# MOM_teensy-breakout_v04.net
KiCad netlist of a schematic drawn in EAGLE
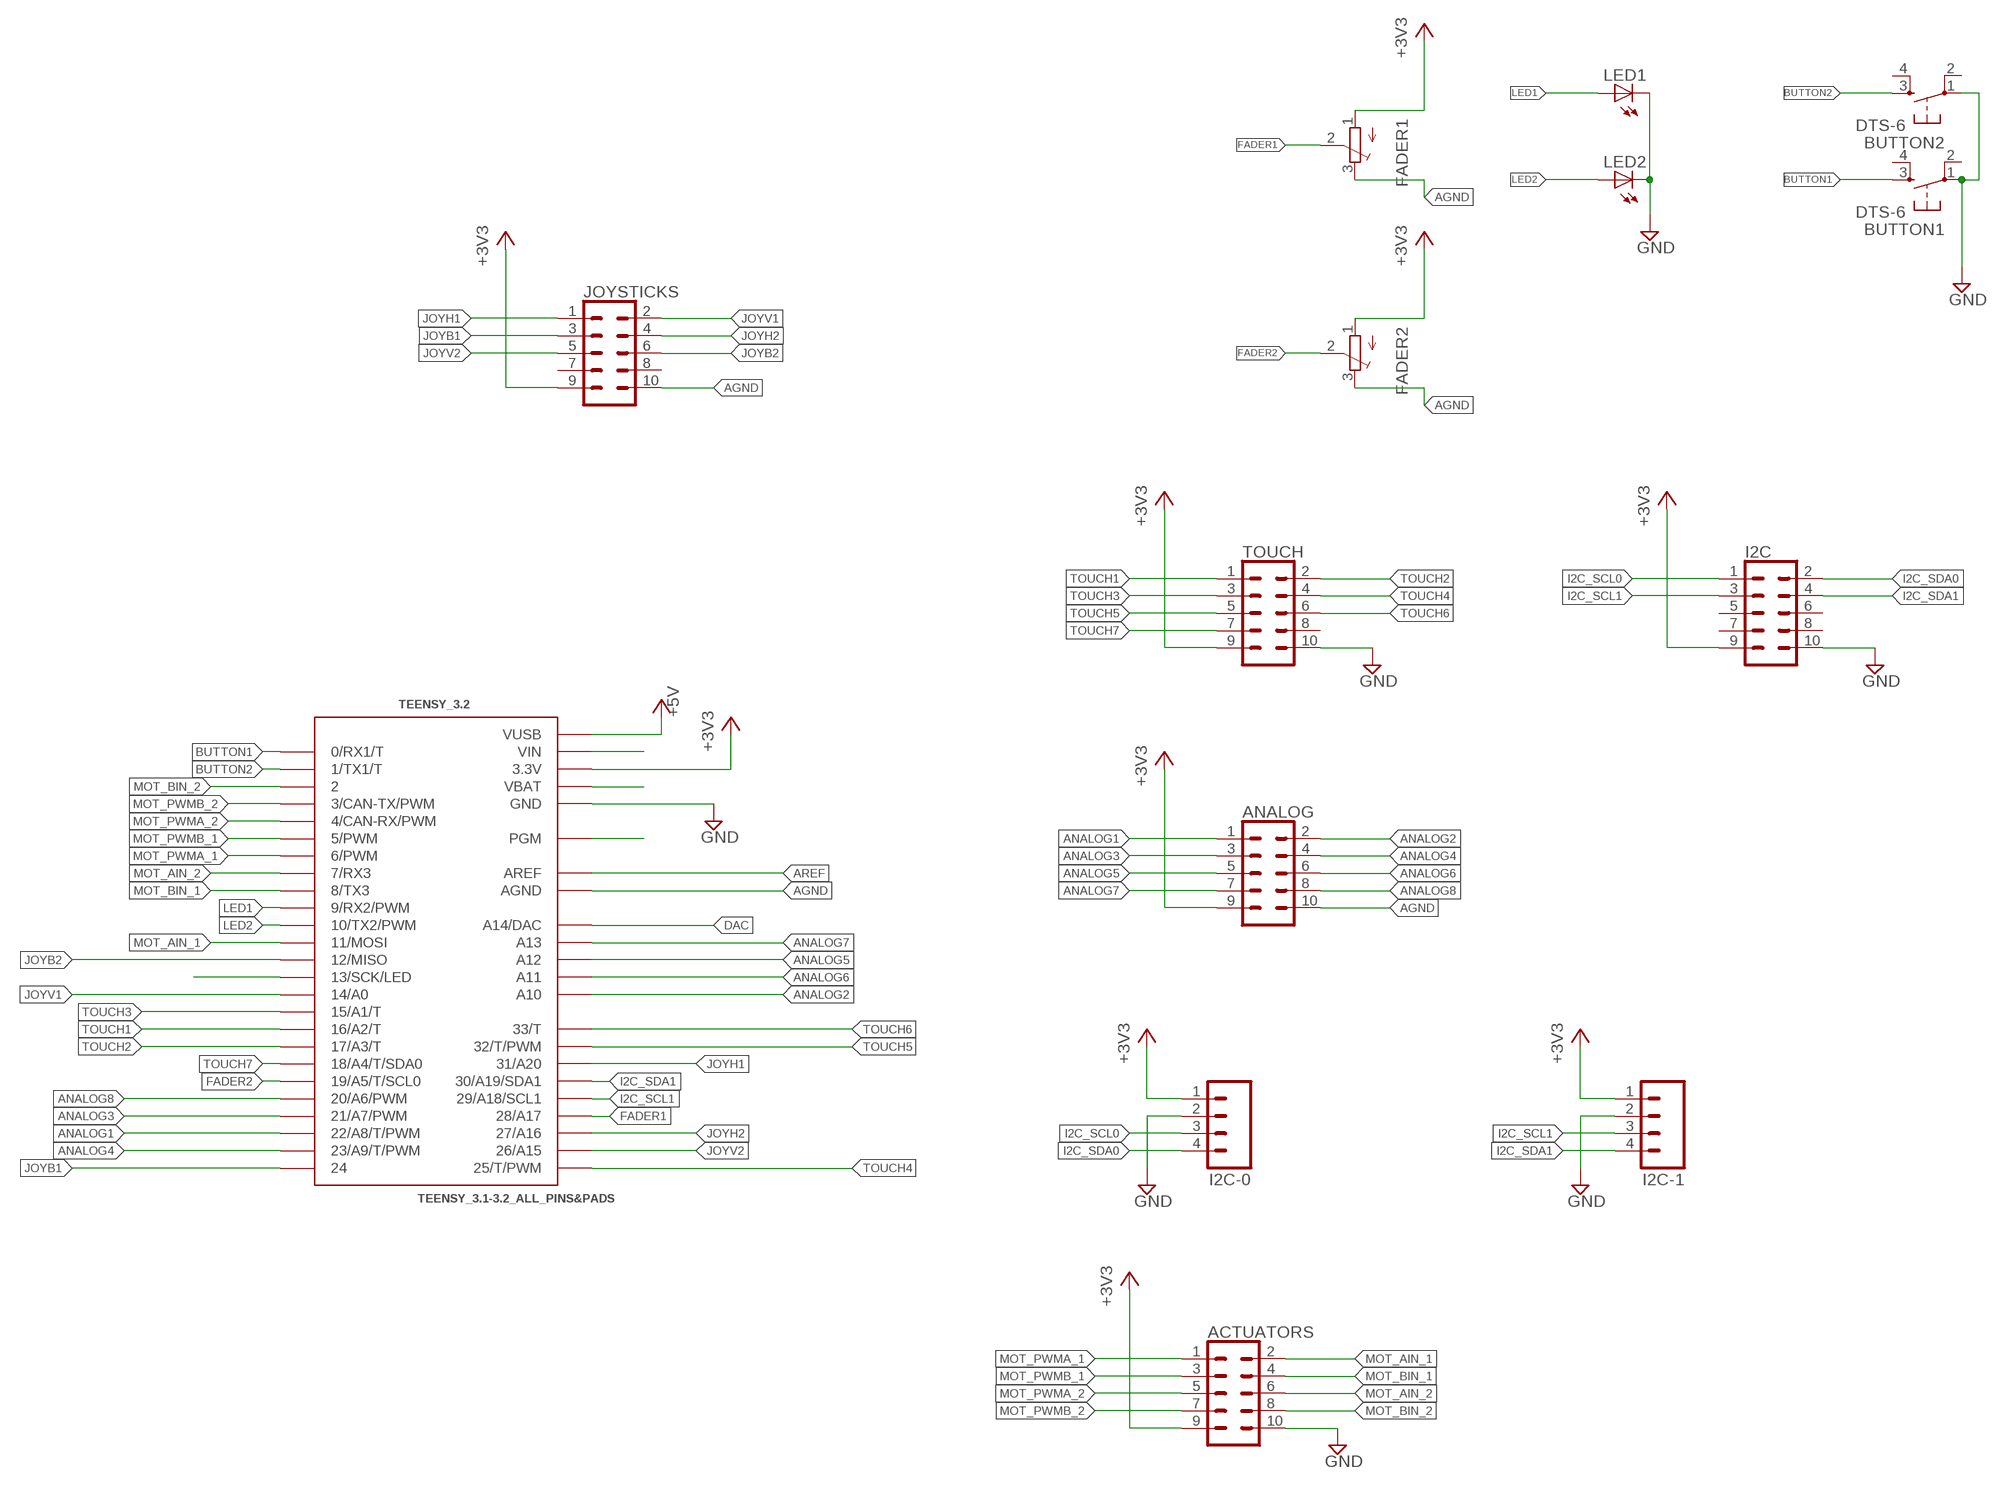
[diagram p0: schematic, sheet 1]

(export (version "E")
  (design (tool "Eeschema 10.0.6"))
  (components
    (comp (ref "ACTUATORS")
      (value "CONN_05X2SHD_LOCK")
      (footprint "eagle-import:2X5-SHROUDED_LOCK")
      (libsource (lib "eagle-import") (part "CONN_05X2SHD_LOCK"))
    )
    (comp (ref "ANALOG")
      (value "CONN_05X2SHD_LOCK")
      (footprint "eagle-import:2X5-SHROUDED_LOCK")
      (libsource (lib "eagle-import") (part "CONN_05X2SHD_LOCK"))
    )
    (comp (ref "BUTTON1")
      (value "DTS-6")
      (footprint "eagle-import:DTS-6")
      (libsource (lib "eagle-import") (part "DTS-6"))
    )
    (comp (ref "BUTTON2")
      (value "DTS-6")
      (footprint "eagle-import:DTS-6")
      (libsource (lib "eagle-import") (part "DTS-6"))
    )
    (comp (ref "FADER1")
      (value "TRIMPOT3386")
      (footprint "eagle-import:TRIM-3386")
      (libsource (lib "eagle-import") (part "TRIMPOT3386"))
    )
    (comp (ref "FADER2")
      (value "TRIMPOT3386")
      (footprint "eagle-import:TRIM-3386")
      (libsource (lib "eagle-import") (part "TRIMPOT3386"))
    )
    (comp (ref "I2C")
      (value "CONN_05X2SHD_LOCK")
      (footprint "eagle-import:2X5-SHROUDED_LOCK")
      (libsource (lib "eagle-import") (part "CONN_05X2SHD_LOCK"))
    )
    (comp (ref "I2C-0")
      (value "M04LOCK")
      (footprint "eagle-import:1X04_LOCK")
      (libsource (lib "eagle-import") (part "M04LOCK"))
    )
    (comp (ref "I2C-1")
      (value "M04LOCK")
      (footprint "eagle-import:1X04_LOCK")
      (libsource (lib "eagle-import") (part "M04LOCK"))
    )
    (comp (ref "JOYSTICKS")
      (value "CONN_05X2SHD_LOCK")
      (footprint "eagle-import:2X5-SHROUDED_LOCK")
      (libsource (lib "eagle-import") (part "CONN_05X2SHD_LOCK"))
    )
    (comp (ref "LED1")
      (value "LED3MM")
      (footprint "eagle-import:LED3MM")
      (libsource (lib "eagle-import") (part "LED3MM"))
    )
    (comp (ref "LED2")
      (value "LED3MM")
      (footprint "eagle-import:LED3MM")
      (libsource (lib "eagle-import") (part "LED3MM"))
    )
    (comp (ref "TEENSY_3.2")
      (value "TEENSY_3.1-3.2_ALL_PINS&PADS")
      (footprint "eagle-import:TEENSY_3.0-3.2_ALL_PINS_&_PADS")
      (libsource (lib "eagle-import") (part "TEENSY_3.1-3.2_ALL_PINS&PADS"))
    )
    (comp (ref "TOUCH")
      (value "CONN_05X2SHD_LOCK")
      (footprint "eagle-import:2X5-SHROUDED_LOCK")
      (libsource (lib "eagle-import") (part "CONN_05X2SHD_LOCK"))
    )
  )
  (nets
    (net (code "1") (name "+3V3") (class "Default")
      (node (ref "ACTUATORS") (pin "9") (pinfunction "9_9") (pintype "passive"))
      (node (ref "ANALOG") (pin "9") (pinfunction "9_9") (pintype "passive"))
      (node (ref "FADER1") (pin "1") (pinfunction "A_1") (pintype "passive"))
      (node (ref "FADER2") (pin "1") (pinfunction "A_1") (pintype "passive"))
      (node (ref "I2C") (pin "9") (pinfunction "9_9") (pintype "passive"))
      (node (ref "I2C-0") (pin "1") (pinfunction "1_1") (pintype "passive"))
      (node (ref "I2C-1") (pin "1") (pinfunction "1_1") (pintype "passive"))
      (node (ref "JOYSTICKS") (pin "9") (pinfunction "9_9") (pintype "passive"))
      (node (ref "TEENSY_3.2") (pin "3.3V") (pinfunction "3.3V_3.3V") (pintype "power_in"))
      (node (ref "TEENSY_3.2") (pin "3.3V1") (pinfunction "3.3V_3.3V1") (pintype "power_in"))
      (node (ref "TEENSY_3.2") (pin "3.3V2") (pinfunction "3.3V_3.3V2") (pintype "power_in"))
      (node (ref "TOUCH") (pin "9") (pinfunction "9_9") (pintype "passive"))
    )
    (net (code "2") (name "+5V") (class "Default")
      (node (ref "TEENSY_3.2") (pin "VUSB") (pinfunction "VUSB_VUSB") (pintype "power_in"))
    )
    (net (code "3") (name "AGND") (class "Default")
      (node (ref "ANALOG") (pin "10") (pinfunction "10_10") (pintype "passive"))
      (node (ref "FADER1") (pin "3") (pinfunction "E_3") (pintype "passive"))
      (node (ref "FADER2") (pin "3") (pinfunction "E_3") (pintype "passive"))
      (node (ref "JOYSTICKS") (pin "10") (pinfunction "10_10") (pintype "passive"))
      (node (ref "TEENSY_3.2") (pin "AGND") (pinfunction "AGND_AGND") (pintype "power_in"))
    )
    (net (code "4") (name "ANALOG1") (class "Default")
      (node (ref "ANALOG") (pin "1") (pinfunction "1_1") (pintype "passive"))
      (node (ref "TEENSY_3.2") (pin "22/A8") (pinfunction "22/A8/T/PWM_22/A8") (pintype "bidirectional"))
    )
    (net (code "5") (name "ANALOG2") (class "Default")
      (node (ref "ANALOG") (pin "2") (pinfunction "2_2") (pintype "passive"))
      (node (ref "TEENSY_3.2") (pin "A10") (pinfunction "A10_A10") (pintype "bidirectional"))
    )
    (net (code "6") (name "ANALOG3") (class "Default")
      (node (ref "ANALOG") (pin "3") (pinfunction "3_3") (pintype "passive"))
      (node (ref "TEENSY_3.2") (pin "21/A7") (pinfunction "21/A7/PWM_21/A7") (pintype "bidirectional"))
    )
    (net (code "7") (name "ANALOG4") (class "Default")
      (node (ref "ANALOG") (pin "4") (pinfunction "4_4") (pintype "passive"))
      (node (ref "TEENSY_3.2") (pin "23/A9") (pinfunction "23/A9/T/PWM_23/A9") (pintype "bidirectional"))
    )
    (net (code "8") (name "ANALOG5") (class "Default")
      (node (ref "ANALOG") (pin "5") (pinfunction "5_5") (pintype "passive"))
      (node (ref "TEENSY_3.2") (pin "A12") (pinfunction "A12_A12") (pintype "bidirectional"))
    )
    (net (code "9") (name "ANALOG6") (class "Default")
      (node (ref "ANALOG") (pin "6") (pinfunction "6_6") (pintype "passive"))
      (node (ref "TEENSY_3.2") (pin "A11") (pinfunction "A11_A11") (pintype "bidirectional"))
    )
    (net (code "10") (name "ANALOG7") (class "Default")
      (node (ref "ANALOG") (pin "7") (pinfunction "7_7") (pintype "passive"))
      (node (ref "TEENSY_3.2") (pin "A13") (pinfunction "A13_A13") (pintype "bidirectional"))
    )
    (net (code "11") (name "ANALOG8") (class "Default")
      (node (ref "ANALOG") (pin "8") (pinfunction "8_8") (pintype "passive"))
      (node (ref "TEENSY_3.2") (pin "20/A6") (pinfunction "20/A6/PWM_20/A6") (pintype "bidirectional"))
    )
    (net (code "12") (name "AREF") (class "Default")
      (node (ref "TEENSY_3.2") (pin "AREF") (pinfunction "AREF_AREF") (pintype "power_in"))
    )
    (net (code "13") (name "BUTTON1") (class "Default")
      (node (ref "BUTTON1") (pin "3") (pinfunction "3_3") (pintype "passive"))
      (node (ref "TEENSY_3.2") (pin "0") (pinfunction "0/RX1/T_0") (pintype "bidirectional"))
    )
    (net (code "14") (name "BUTTON2") (class "Default")
      (node (ref "BUTTON2") (pin "3") (pinfunction "3_3") (pintype "passive"))
      (node (ref "TEENSY_3.2") (pin "1") (pinfunction "1/TX1/T_1") (pintype "bidirectional"))
    )
    (net (code "15") (name "DAC") (class "Default")
      (node (ref "TEENSY_3.2") (pin "RESET/DAC") (pinfunction "A14/DAC_RESET/DAC") (pintype "bidirectional"))
    )
    (net (code "16") (name "FADER1") (class "Default")
      (node (ref "FADER1") (pin "2") (pinfunction "S_2") (pintype "passive"))
      (node (ref "TEENSY_3.2") (pin "28") (pinfunction "28/A17_28") (pintype "bidirectional"))
    )
    (net (code "17") (name "FADER2") (class "Default")
      (node (ref "FADER2") (pin "2") (pinfunction "S_2") (pintype "passive"))
      (node (ref "TEENSY_3.2") (pin "19/A5") (pinfunction "19/A5/T/SCL0_19/A5") (pintype "bidirectional"))
    )
    (net (code "18") (name "GND") (class "Default")
      (node (ref "ACTUATORS") (pin "10") (pinfunction "10_10") (pintype "passive"))
      (node (ref "BUTTON1") (pin "1") (pinfunction "1_1") (pintype "passive"))
      (node (ref "BUTTON2") (pin "1") (pinfunction "1_1") (pintype "passive"))
      (node (ref "I2C") (pin "10") (pinfunction "10_10") (pintype "passive"))
      (node (ref "I2C-0") (pin "2") (pinfunction "2_2") (pintype "passive"))
      (node (ref "I2C-1") (pin "2") (pinfunction "2_2") (pintype "passive"))
      (node (ref "LED1") (pin "K") (pinfunction "C_K") (pintype "passive"))
      (node (ref "LED2") (pin "K") (pinfunction "C_K") (pintype "passive"))
      (node (ref "TEENSY_3.2") (pin "GND") (pinfunction "GND_GND") (pintype "power_in"))
      (node (ref "TEENSY_3.2") (pin "GND1") (pinfunction "GND_GND1") (pintype "power_in"))
      (node (ref "TEENSY_3.2") (pin "GND2") (pinfunction "GND_GND2") (pintype "power_in"))
      (node (ref "TOUCH") (pin "10") (pinfunction "10_10") (pintype "passive"))
    )
    (net (code "19") (name "I2C_SCL0") (class "Default")
      (node (ref "I2C") (pin "1") (pinfunction "1_1") (pintype "passive"))
      (node (ref "I2C-0") (pin "3") (pinfunction "3_3") (pintype "passive"))
    )
    (net (code "20") (name "I2C_SCL1") (class "Default")
      (node (ref "I2C") (pin "3") (pinfunction "3_3") (pintype "passive"))
      (node (ref "I2C-1") (pin "3") (pinfunction "3_3") (pintype "passive"))
      (node (ref "TEENSY_3.2") (pin "29") (pinfunction "29/A18/SCL1_29") (pintype "bidirectional"))
    )
    (net (code "21") (name "I2C_SDA0") (class "Default")
      (node (ref "I2C") (pin "2") (pinfunction "2_2") (pintype "passive"))
      (node (ref "I2C-0") (pin "4") (pinfunction "4_4") (pintype "passive"))
    )
    (net (code "22") (name "I2C_SDA1") (class "Default")
      (node (ref "I2C") (pin "4") (pinfunction "4_4") (pintype "passive"))
      (node (ref "I2C-1") (pin "4") (pinfunction "4_4") (pintype "passive"))
      (node (ref "TEENSY_3.2") (pin "30") (pinfunction "30/A19/SDA1_30") (pintype "bidirectional"))
    )
    (net (code "23") (name "JOYB1") (class "Default")
      (node (ref "JOYSTICKS") (pin "3") (pinfunction "3_3") (pintype "passive"))
      (node (ref "TEENSY_3.2") (pin "24") (pinfunction "24_24") (pintype "bidirectional"))
    )
    (net (code "24") (name "JOYB2") (class "Default")
      (node (ref "JOYSTICKS") (pin "6") (pinfunction "6_6") (pintype "passive"))
      (node (ref "TEENSY_3.2") (pin "12") (pinfunction "12/MISO_12") (pintype "bidirectional"))
    )
    (net (code "25") (name "JOYH1") (class "Default")
      (node (ref "JOYSTICKS") (pin "1") (pinfunction "1_1") (pintype "passive"))
      (node (ref "TEENSY_3.2") (pin "31") (pinfunction "31/A20_31") (pintype "bidirectional"))
    )
    (net (code "26") (name "JOYH2") (class "Default")
      (node (ref "JOYSTICKS") (pin "4") (pinfunction "4_4") (pintype "passive"))
      (node (ref "TEENSY_3.2") (pin "27") (pinfunction "27/A16_27") (pintype "bidirectional"))
    )
    (net (code "27") (name "JOYV1") (class "Default")
      (node (ref "JOYSTICKS") (pin "2") (pinfunction "2_2") (pintype "passive"))
      (node (ref "TEENSY_3.2") (pin "14/A0") (pinfunction "14/A0_14/A0") (pintype "bidirectional"))
    )
    (net (code "28") (name "JOYV2") (class "Default")
      (node (ref "JOYSTICKS") (pin "5") (pinfunction "5_5") (pintype "passive"))
      (node (ref "TEENSY_3.2") (pin "26") (pinfunction "26/A15_26") (pintype "bidirectional"))
    )
    (net (code "29") (name "LED1") (class "Default")
      (node (ref "LED1") (pin "A") (pinfunction "A_A") (pintype "passive"))
      (node (ref "TEENSY_3.2") (pin "9") (pinfunction "9/RX2/PWM_9") (pintype "bidirectional"))
    )
    (net (code "30") (name "LED2") (class "Default")
      (node (ref "LED2") (pin "A") (pinfunction "A_A") (pintype "passive"))
      (node (ref "TEENSY_3.2") (pin "10") (pinfunction "10/TX2/PWM_10") (pintype "bidirectional"))
    )
    (net (code "31") (name "MOT_AIN_1") (class "Default")
      (node (ref "ACTUATORS") (pin "2") (pinfunction "2_2") (pintype "passive"))
      (node (ref "TEENSY_3.2") (pin "11") (pinfunction "11/MOSI_11") (pintype "bidirectional"))
    )
    (net (code "32") (name "MOT_AIN_2") (class "Default")
      (node (ref "ACTUATORS") (pin "6") (pinfunction "6_6") (pintype "passive"))
      (node (ref "TEENSY_3.2") (pin "7") (pinfunction "7/RX3_7") (pintype "bidirectional"))
    )
    (net (code "33") (name "MOT_BIN_1") (class "Default")
      (node (ref "ACTUATORS") (pin "4") (pinfunction "4_4") (pintype "passive"))
      (node (ref "TEENSY_3.2") (pin "8") (pinfunction "8/TX3_8") (pintype "bidirectional"))
    )
    (net (code "34") (name "MOT_BIN_2") (class "Default")
      (node (ref "ACTUATORS") (pin "8") (pinfunction "8_8") (pintype "passive"))
      (node (ref "TEENSY_3.2") (pin "2") (pinfunction "2_2") (pintype "bidirectional"))
    )
    (net (code "35") (name "MOT_PWMA_1") (class "Default")
      (node (ref "ACTUATORS") (pin "1") (pinfunction "1_1") (pintype "passive"))
      (node (ref "TEENSY_3.2") (pin "6") (pinfunction "6/PWM_6") (pintype "bidirectional"))
    )
    (net (code "36") (name "MOT_PWMA_2") (class "Default")
      (node (ref "ACTUATORS") (pin "5") (pinfunction "5_5") (pintype "passive"))
      (node (ref "TEENSY_3.2") (pin "4") (pinfunction "4/CAN-RX/PWM_4") (pintype "bidirectional"))
    )
    (net (code "37") (name "MOT_PWMB_1") (class "Default")
      (node (ref "ACTUATORS") (pin "3") (pinfunction "3_3") (pintype "passive"))
      (node (ref "TEENSY_3.2") (pin "5") (pinfunction "5/PWM_5") (pintype "bidirectional"))
    )
    (net (code "38") (name "MOT_PWMB_2") (class "Default")
      (node (ref "ACTUATORS") (pin "7") (pinfunction "7_7") (pintype "passive"))
      (node (ref "TEENSY_3.2") (pin "3") (pinfunction "3/CAN-TX/PWM_3") (pintype "bidirectional"))
    )
    (net (code "39") (name "TOUCH1") (class "Default")
      (node (ref "TEENSY_3.2") (pin "16/A2") (pinfunction "16/A2/T_16/A2") (pintype "bidirectional"))
      (node (ref "TOUCH") (pin "1") (pinfunction "1_1") (pintype "passive"))
    )
    (net (code "40") (name "TOUCH2") (class "Default")
      (node (ref "TEENSY_3.2") (pin "17/A3") (pinfunction "17/A3/T_17/A3") (pintype "bidirectional"))
      (node (ref "TOUCH") (pin "2") (pinfunction "2_2") (pintype "passive"))
    )
    (net (code "41") (name "TOUCH3") (class "Default")
      (node (ref "TEENSY_3.2") (pin "15/A1") (pinfunction "15/A1/T_15/A1") (pintype "bidirectional"))
      (node (ref "TOUCH") (pin "3") (pinfunction "3_3") (pintype "passive"))
    )
    (net (code "42") (name "TOUCH4") (class "Default")
      (node (ref "TEENSY_3.2") (pin "25") (pinfunction "25/T/PWM_25") (pintype "bidirectional"))
      (node (ref "TOUCH") (pin "4") (pinfunction "4_4") (pintype "passive"))
    )
    (net (code "43") (name "TOUCH5") (class "Default")
      (node (ref "TEENSY_3.2") (pin "32") (pinfunction "32/T/PWM_32") (pintype "bidirectional"))
      (node (ref "TOUCH") (pin "5") (pinfunction "5_5") (pintype "passive"))
    )
    (net (code "44") (name "TOUCH6") (class "Default")
      (node (ref "TEENSY_3.2") (pin "33") (pinfunction "33/T_33") (pintype "bidirectional"))
      (node (ref "TOUCH") (pin "6") (pinfunction "6_6") (pintype "passive"))
    )
    (net (code "45") (name "TOUCH7") (class "Default")
      (node (ref "TEENSY_3.2") (pin "18/A4") (pinfunction "18/A4/T/SDA0_18/A4") (pintype "bidirectional"))
      (node (ref "TOUCH") (pin "7") (pinfunction "7_7") (pintype "passive"))
    )
    (net (code "46") (name "unconnected-(BUTTON1-Pad2)") (class "Default")
      (node (ref "BUTTON1") (pin "2") (pinfunction "2_2") (pintype "passive"))
    )
    (net (code "47") (name "unconnected-(BUTTON1-Pad4)") (class "Default")
      (node (ref "BUTTON1") (pin "4") (pinfunction "4_4") (pintype "passive"))
    )
    (net (code "48") (name "unconnected-(BUTTON2-Pad2)") (class "Default")
      (node (ref "BUTTON2") (pin "2") (pinfunction "2_2") (pintype "passive"))
    )
    (net (code "49") (name "unconnected-(BUTTON2-Pad4)") (class "Default")
      (node (ref "BUTTON2") (pin "4") (pinfunction "4_4") (pintype "passive"))
    )
    (net (code "50") (name "unconnected-(I2C-Pad5)") (class "Default")
      (node (ref "I2C") (pin "5") (pinfunction "5_5") (pintype "passive"))
    )
    (net (code "51") (name "unconnected-(I2C-Pad6)") (class "Default")
      (node (ref "I2C") (pin "6") (pinfunction "6_6") (pintype "passive"))
    )
    (net (code "52") (name "unconnected-(I2C-Pad7)") (class "Default")
      (node (ref "I2C") (pin "7") (pinfunction "7_7") (pintype "passive"))
    )
    (net (code "53") (name "unconnected-(I2C-Pad8)") (class "Default")
      (node (ref "I2C") (pin "8") (pinfunction "8_8") (pintype "passive"))
    )
    (net (code "54") (name "unconnected-(JOYSTICKS-Pad7)") (class "Default")
      (node (ref "JOYSTICKS") (pin "7") (pinfunction "7_7") (pintype "passive"))
    )
    (net (code "55") (name "unconnected-(JOYSTICKS-Pad8)") (class "Default")
      (node (ref "JOYSTICKS") (pin "8") (pinfunction "8_8") (pintype "passive"))
    )
    (net (code "56") (name "unconnected-(TEENSY_3.2-13{slash}SCK{slash}LED-Pad13)") (class "Default")
      (node (ref "TEENSY_3.2") (pin "13") (pinfunction "13/SCK/LED_13") (pintype "bidirectional"))
    )
    (net (code "57") (name "unconnected-(TEENSY_3.2-PadPGM)") (class "Default")
      (node (ref "TEENSY_3.2") (pin "PGM") (pinfunction "PGM_PGM") (pintype "bidirectional"))
    )
    (net (code "58") (name "unconnected-(TEENSY_3.2-PadVBAT)") (class "Default")
      (node (ref "TEENSY_3.2") (pin "VBAT") (pinfunction "VBAT_VBAT") (pintype "power_in"))
    )
    (net (code "59") (name "unconnected-(TEENSY_3.2-PadVIN)") (class "Default")
      (node (ref "TEENSY_3.2") (pin "VIN") (pinfunction "VIN_VIN") (pintype "power_in"))
    )
    (net (code "60") (name "unconnected-(TOUCH-Pad8)") (class "Default")
      (node (ref "TOUCH") (pin "8") (pinfunction "8_8") (pintype "passive"))
    )
  )
)
